# Stemma_Notecard.net
KiCad netlist of a schematic drawn in EAGLE
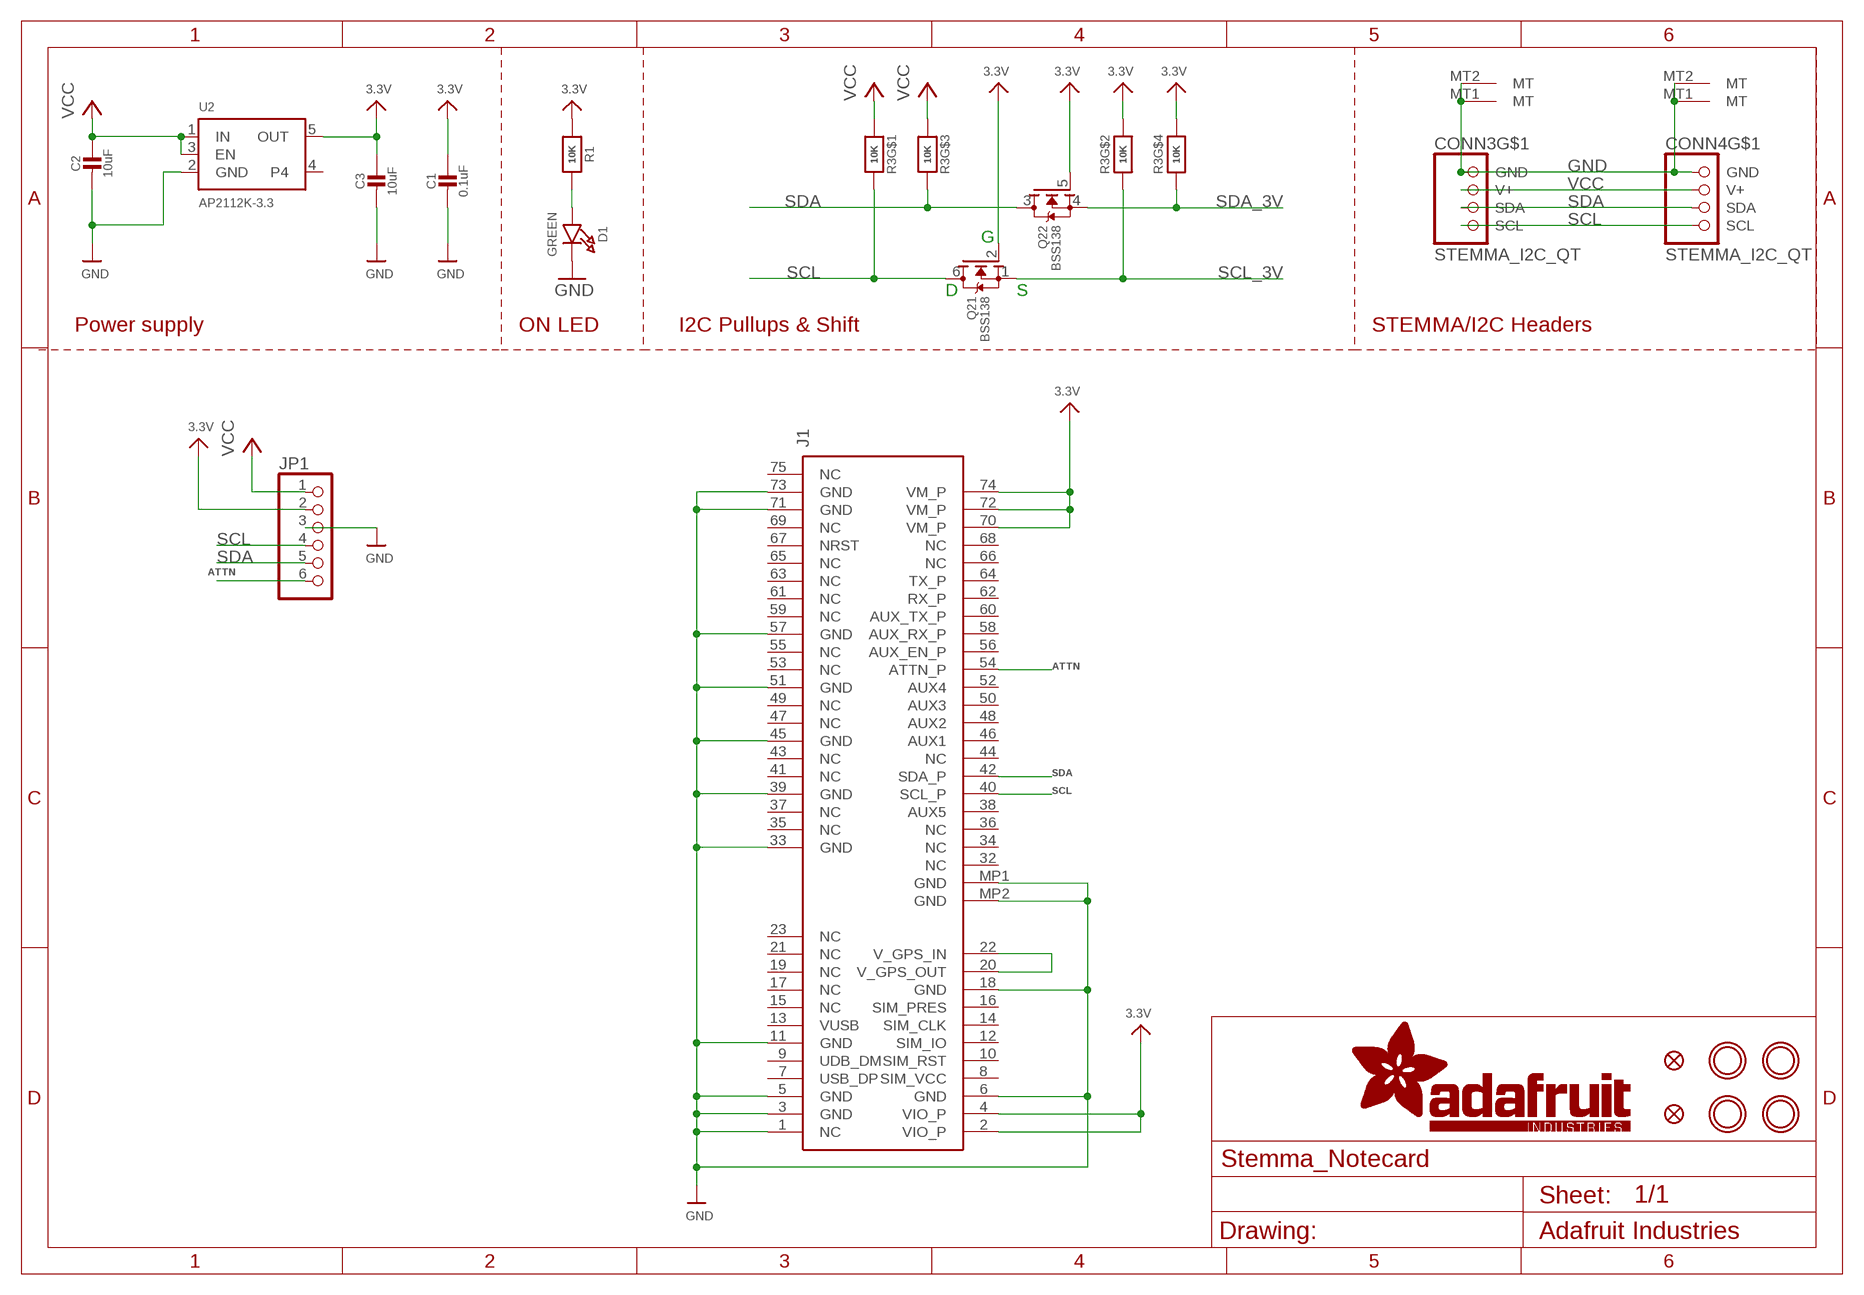
[diagram p0: schematic, sheet 1]

(export (version "E")
  (design (tool "Eeschema 10.0.6"))
  (components
    (comp (ref "C1")
      (value "0.1uF")
      (footprint "eagle-import:0603-NO")
      (libsource (lib "eagle-import") (part "CAP_CERAMIC0603_NO"))
    )
    (comp (ref "C2")
      (value "10uF")
      (footprint "eagle-import:0805-NO")
      (libsource (lib "eagle-import") (part "CAP_CERAMIC0805-NOOUTLINE"))
    )
    (comp (ref "C3")
      (value "10uF")
      (footprint "eagle-import:0805-NO")
      (libsource (lib "eagle-import") (part "CAP_CERAMIC0805-NOOUTLINE"))
    )
    (comp (ref "CONN3")
      (value "STEMMA_I2C_QT")
      (footprint "eagle-import:JST_SH4")
      (libsource (lib "eagle-import") (part "STEMMA_I2C_QT"))
    )
    (comp (ref "CONN4")
      (value "STEMMA_I2C_QT")
      (footprint "eagle-import:JST_SH4")
      (libsource (lib "eagle-import") (part "STEMMA_I2C_QT"))
    )
    (comp (ref "D1")
      (value "GREEN")
      (footprint "eagle-import:CHIPLED_0603_NOOUTLINE")
      (libsource (lib "eagle-import") (part "LED0603_NOOUTLINE"))
    )
    (comp (ref "FID3")
      (value "FIDUCIAL_1MM")
      (footprint "eagle-import:FIDUCIAL_1MM")
      (libsource (lib "eagle-import") (part "FIDUCIAL_1MM"))
    )
    (comp (ref "FID4")
      (value "FIDUCIAL_1MM")
      (footprint "eagle-import:FIDUCIAL_1MM")
      (libsource (lib "eagle-import") (part "FIDUCIAL_1MM"))
    )
    (comp (ref "J1")
      (value "MDT420E01001NOTECARD")
      (footprint "eagle-import:NOTECARD")
      (libsource (lib "eagle-import") (part "MDT420E01001NOTECARD"))
    )
    (comp (ref "JP1")
      (value "HEADER-1X670MIL")
      (footprint "eagle-import:1X06_ROUND_70")
      (libsource (lib "eagle-import") (part "HEADER-1X670MIL"))
    )
    (comp (ref "Q2")
      (value "BSS138")
      (footprint "eagle-import:SOT363")
      (libsource (lib "eagle-import") (part "MOSFET-N_DUAL"))
    )
    (comp (ref "R1")
      (value "10K")
      (footprint "eagle-import:0603-NO")
      (libsource (lib "eagle-import") (part "RESISTOR_0603_NOOUT"))
    )
    (comp (ref "R3")
      (value "10K")
      (footprint "eagle-import:RESPACK_4X0603")
      (libsource (lib "eagle-import") (part "RESISTOR_4PACK"))
    )
    (comp (ref "U$1")
      (value "MOUNTINGHOLE2.5")
      (footprint "eagle-import:MOUNTINGHOLE_2.5_PLATED")
      (libsource (lib "eagle-import") (part "MOUNTINGHOLE2.5"))
    )
    (comp (ref "U$17")
      (value "MOUNTINGHOLE2.5")
      (footprint "eagle-import:MOUNTINGHOLE_2.5_PLATED")
      (libsource (lib "eagle-import") (part "MOUNTINGHOLE2.5"))
    )
    (comp (ref "U$19")
      (value "MOUNTINGHOLE2.5")
      (footprint "eagle-import:MOUNTINGHOLE_2.5_PLATED")
      (libsource (lib "eagle-import") (part "MOUNTINGHOLE2.5"))
    )
    (comp (ref "U$21")
      (value "MOUNTINGHOLE2.5")
      (footprint "eagle-import:MOUNTINGHOLE_2.5_PLATED")
      (libsource (lib "eagle-import") (part "MOUNTINGHOLE2.5"))
    )
    (comp (ref "U2")
      (value "AP2112K-3.3")
      (footprint "eagle-import:SOT23-5")
      (libsource (lib "eagle-import") (part "VREG_SOT23-5"))
    )
  )
  (nets
    (net (code "1") (name "/SCL_3V") (class "Default")
      (node (ref "Q2") (pin "1") (pinfunction "S_1") (pintype "bidirectional"))
      (node (ref "R3") (pin "7") (pinfunction "2_7") (pintype "passive"))
    )
    (net (code "2") (name "/SDA_3V") (class "Default")
      (node (ref "Q2") (pin "4") (pinfunction "S_4") (pintype "bidirectional"))
      (node (ref "R3") (pin "5") (pinfunction "2_5") (pintype "passive"))
    )
    (net (code "3") (name "3.3V") (class "Default")
      (node (ref "C1") (pin "1") (pinfunction "1_1") (pintype "passive"))
      (node (ref "C3") (pin "1") (pinfunction "1_1") (pintype "passive"))
      (node (ref "J1") (pin "2") (pinfunction "VIO_P_2") (pintype "bidirectional"))
      (node (ref "J1") (pin "4") (pinfunction "VIO_P_4") (pintype "bidirectional"))
      (node (ref "J1") (pin "70") (pinfunction "VM_P_70") (pintype "bidirectional"))
      (node (ref "J1") (pin "72") (pinfunction "VM_P_72") (pintype "bidirectional"))
      (node (ref "J1") (pin "74") (pinfunction "VM_P_74") (pintype "bidirectional"))
      (node (ref "JP1") (pin "2") (pinfunction "2_2") (pintype "passive"))
      (node (ref "Q2") (pin "2") (pinfunction "G_2") (pintype "bidirectional"))
      (node (ref "Q2") (pin "5") (pinfunction "G_5") (pintype "bidirectional"))
      (node (ref "R1") (pin "1") (pinfunction "1_1") (pintype "passive"))
      (node (ref "R3") (pin "2") (pinfunction "1_2") (pintype "passive"))
      (node (ref "R3") (pin "4") (pinfunction "1_4") (pintype "passive"))
      (node (ref "U2") (pin "5") (pinfunction "OUT_5") (pintype "power_in"))
    )
    (net (code "4") (name "ATTN") (class "Default")
      (node (ref "J1") (pin "54") (pinfunction "ATTN_P_54") (pintype "bidirectional"))
      (node (ref "JP1") (pin "6") (pinfunction "6_6") (pintype "passive"))
    )
    (net (code "5") (name "GND") (class "Default")
      (node (ref "C1") (pin "2") (pinfunction "2_2") (pintype "passive"))
      (node (ref "C2") (pin "2") (pinfunction "2_2") (pintype "passive"))
      (node (ref "C3") (pin "2") (pinfunction "2_2") (pintype "passive"))
      (node (ref "CONN3") (pin "1") (pinfunction "GND_1") (pintype "passive"))
      (node (ref "CONN3") (pin "MT1") (pinfunction "MT_MT1") (pintype "bidirectional"))
      (node (ref "CONN3") (pin "MT2") (pinfunction "MT_MT2") (pintype "bidirectional"))
      (node (ref "CONN4") (pin "1") (pinfunction "GND_1") (pintype "passive"))
      (node (ref "CONN4") (pin "MT1") (pinfunction "MT_MT1") (pintype "bidirectional"))
      (node (ref "CONN4") (pin "MT2") (pinfunction "MT_MT2") (pintype "bidirectional"))
      (node (ref "D1") (pin "C") (pinfunction "C_C") (pintype "passive"))
      (node (ref "J1") (pin "1") (pinfunction "NC_1") (pintype "bidirectional"))
      (node (ref "J1") (pin "11") (pinfunction "GND_11") (pintype "bidirectional"))
      (node (ref "J1") (pin "18") (pinfunction "GND_18") (pintype "bidirectional"))
      (node (ref "J1") (pin "3") (pinfunction "GND_3") (pintype "bidirectional"))
      (node (ref "J1") (pin "33") (pinfunction "GND_33") (pintype "bidirectional"))
      (node (ref "J1") (pin "39") (pinfunction "GND_39") (pintype "bidirectional"))
      (node (ref "J1") (pin "45") (pinfunction "GND_45") (pintype "bidirectional"))
      (node (ref "J1") (pin "5") (pinfunction "GND_5") (pintype "bidirectional"))
      (node (ref "J1") (pin "51") (pinfunction "GND_51") (pintype "bidirectional"))
      (node (ref "J1") (pin "57") (pinfunction "GND_57") (pintype "bidirectional"))
      (node (ref "J1") (pin "6") (pinfunction "GND_6") (pintype "bidirectional"))
      (node (ref "J1") (pin "71") (pinfunction "GND_71") (pintype "bidirectional"))
      (node (ref "J1") (pin "73") (pinfunction "GND_73") (pintype "bidirectional"))
      (node (ref "J1") (pin "MP1") (pinfunction "GND_MP1") (pintype "power_in"))
      (node (ref "J1") (pin "MP2") (pinfunction "GND_MP2") (pintype "bidirectional"))
      (node (ref "JP1") (pin "3") (pinfunction "3_3") (pintype "passive"))
      (node (ref "U2") (pin "2") (pinfunction "GND_2") (pintype "power_in"))
    )
    (net (code "6") (name "Net-(D1-PadA)") (class "Default")
      (node (ref "D1") (pin "A") (pinfunction "A_A") (pintype "passive"))
      (node (ref "R1") (pin "2") (pinfunction "2_2") (pintype "passive"))
    )
    (net (code "7") (name "Net-(J1-V_GPS_IN)") (class "Default")
      (node (ref "J1") (pin "20") (pinfunction "V_GPS_OUT_20") (pintype "bidirectional"))
      (node (ref "J1") (pin "22") (pinfunction "V_GPS_IN_22") (pintype "bidirectional"))
    )
    (net (code "8") (name "SCL") (class "Default")
      (node (ref "CONN3") (pin "4") (pinfunction "SCL_4") (pintype "passive"))
      (node (ref "CONN4") (pin "4") (pinfunction "SCL_4") (pintype "passive"))
      (node (ref "J1") (pin "40") (pinfunction "SCL_P_40") (pintype "bidirectional"))
      (node (ref "JP1") (pin "4") (pinfunction "4_4") (pintype "passive"))
      (node (ref "Q2") (pin "6") (pinfunction "D_6") (pintype "bidirectional"))
      (node (ref "R3") (pin "8") (pinfunction "2_8") (pintype "passive"))
    )
    (net (code "9") (name "SDA") (class "Default")
      (node (ref "CONN3") (pin "3") (pinfunction "SDA_3") (pintype "passive"))
      (node (ref "CONN4") (pin "3") (pinfunction "SDA_3") (pintype "passive"))
      (node (ref "J1") (pin "42") (pinfunction "SDA_P_42") (pintype "bidirectional"))
      (node (ref "JP1") (pin "5") (pinfunction "5_5") (pintype "passive"))
      (node (ref "Q2") (pin "3") (pinfunction "D_3") (pintype "bidirectional"))
      (node (ref "R3") (pin "6") (pinfunction "2_6") (pintype "passive"))
    )
    (net (code "10") (name "VCC") (class "Default")
      (node (ref "C2") (pin "1") (pinfunction "1_1") (pintype "passive"))
      (node (ref "CONN3") (pin "2") (pinfunction "V+_2") (pintype "passive"))
      (node (ref "CONN4") (pin "2") (pinfunction "V+_2") (pintype "passive"))
      (node (ref "JP1") (pin "1") (pinfunction "1_1") (pintype "passive"))
      (node (ref "R3") (pin "1") (pinfunction "1_1") (pintype "passive"))
      (node (ref "R3") (pin "3") (pinfunction "1_3") (pintype "passive"))
      (node (ref "U2") (pin "1") (pinfunction "IN_1") (pintype "power_in"))
      (node (ref "U2") (pin "3") (pinfunction "EN_3") (pintype "input"))
    )
    (net (code "11") (name "unconnected-(J1-AUX1-Pad46)") (class "Default")
      (node (ref "J1") (pin "46") (pinfunction "AUX1_46") (pintype "bidirectional"))
    )
    (net (code "12") (name "unconnected-(J1-AUX2-Pad48)") (class "Default")
      (node (ref "J1") (pin "48") (pinfunction "AUX2_48") (pintype "bidirectional"))
    )
    (net (code "13") (name "unconnected-(J1-AUX3-Pad50)") (class "Default")
      (node (ref "J1") (pin "50") (pinfunction "AUX3_50") (pintype "bidirectional"))
    )
    (net (code "14") (name "unconnected-(J1-AUX4-Pad52)") (class "Default")
      (node (ref "J1") (pin "52") (pinfunction "AUX4_52") (pintype "bidirectional"))
    )
    (net (code "15") (name "unconnected-(J1-AUX5-Pad38)") (class "Default")
      (node (ref "J1") (pin "38") (pinfunction "AUX5_38") (pintype "bidirectional"))
    )
    (net (code "16") (name "unconnected-(J1-AUX_EN_P-Pad56)") (class "Default")
      (node (ref "J1") (pin "56") (pinfunction "AUX_EN_P_56") (pintype "bidirectional"))
    )
    (net (code "17") (name "unconnected-(J1-AUX_RX_P-Pad58)") (class "Default")
      (node (ref "J1") (pin "58") (pinfunction "AUX_RX_P_58") (pintype "bidirectional"))
    )
    (net (code "18") (name "unconnected-(J1-AUX_TX_P-Pad60)") (class "Default")
      (node (ref "J1") (pin "60") (pinfunction "AUX_TX_P_60") (pintype "bidirectional"))
    )
    (net (code "19") (name "unconnected-(J1-NC-Pad15)") (class "Default")
      (node (ref "J1") (pin "15") (pinfunction "NC_15") (pintype "bidirectional"))
    )
    (net (code "20") (name "unconnected-(J1-NC-Pad17)") (class "Default")
      (node (ref "J1") (pin "17") (pinfunction "NC_17") (pintype "bidirectional"))
    )
    (net (code "21") (name "unconnected-(J1-NC-Pad19)") (class "Default")
      (node (ref "J1") (pin "19") (pinfunction "NC_19") (pintype "bidirectional"))
    )
    (net (code "22") (name "unconnected-(J1-NC-Pad21)") (class "Default")
      (node (ref "J1") (pin "21") (pinfunction "NC_21") (pintype "bidirectional"))
    )
    (net (code "23") (name "unconnected-(J1-NC-Pad23)") (class "Default")
      (node (ref "J1") (pin "23") (pinfunction "NC_23") (pintype "bidirectional"))
    )
    (net (code "24") (name "unconnected-(J1-NC-Pad32)") (class "Default")
      (node (ref "J1") (pin "32") (pinfunction "NC_32") (pintype "bidirectional"))
    )
    (net (code "25") (name "unconnected-(J1-NC-Pad34)") (class "Default")
      (node (ref "J1") (pin "34") (pinfunction "NC_34") (pintype "bidirectional"))
    )
    (net (code "26") (name "unconnected-(J1-NC-Pad35)") (class "Default")
      (node (ref "J1") (pin "35") (pinfunction "NC_35") (pintype "bidirectional"))
    )
    (net (code "27") (name "unconnected-(J1-NC-Pad36)") (class "Default")
      (node (ref "J1") (pin "36") (pinfunction "NC_36") (pintype "bidirectional"))
    )
    (net (code "28") (name "unconnected-(J1-NC-Pad37)") (class "Default")
      (node (ref "J1") (pin "37") (pinfunction "NC_37") (pintype "bidirectional"))
    )
    (net (code "29") (name "unconnected-(J1-NC-Pad41)") (class "Default")
      (node (ref "J1") (pin "41") (pinfunction "NC_41") (pintype "bidirectional"))
    )
    (net (code "30") (name "unconnected-(J1-NC-Pad43)") (class "Default")
      (node (ref "J1") (pin "43") (pinfunction "NC_43") (pintype "bidirectional"))
    )
    (net (code "31") (name "unconnected-(J1-NC-Pad44)") (class "Default")
      (node (ref "J1") (pin "44") (pinfunction "NC_44") (pintype "bidirectional"))
    )
    (net (code "32") (name "unconnected-(J1-NC-Pad47)") (class "Default")
      (node (ref "J1") (pin "47") (pinfunction "NC_47") (pintype "bidirectional"))
    )
    (net (code "33") (name "unconnected-(J1-NC-Pad49)") (class "Default")
      (node (ref "J1") (pin "49") (pinfunction "NC_49") (pintype "bidirectional"))
    )
    (net (code "34") (name "unconnected-(J1-NC-Pad53)") (class "Default")
      (node (ref "J1") (pin "53") (pinfunction "NC_53") (pintype "bidirectional"))
    )
    (net (code "35") (name "unconnected-(J1-NC-Pad55)") (class "Default")
      (node (ref "J1") (pin "55") (pinfunction "NC_55") (pintype "bidirectional"))
    )
    (net (code "36") (name "unconnected-(J1-NC-Pad59)") (class "Default")
      (node (ref "J1") (pin "59") (pinfunction "NC_59") (pintype "bidirectional"))
    )
    (net (code "37") (name "unconnected-(J1-NC-Pad61)") (class "Default")
      (node (ref "J1") (pin "61") (pinfunction "NC_61") (pintype "bidirectional"))
    )
    (net (code "38") (name "unconnected-(J1-NC-Pad63)") (class "Default")
      (node (ref "J1") (pin "63") (pinfunction "NC_63") (pintype "bidirectional"))
    )
    (net (code "39") (name "unconnected-(J1-NC-Pad65)") (class "Default")
      (node (ref "J1") (pin "65") (pinfunction "NC_65") (pintype "bidirectional"))
    )
    (net (code "40") (name "unconnected-(J1-NC-Pad66)") (class "Default")
      (node (ref "J1") (pin "66") (pinfunction "NC_66") (pintype "bidirectional"))
    )
    (net (code "41") (name "unconnected-(J1-NC-Pad68)") (class "Default")
      (node (ref "J1") (pin "68") (pinfunction "NC_68") (pintype "bidirectional"))
    )
    (net (code "42") (name "unconnected-(J1-NC-Pad69)") (class "Default")
      (node (ref "J1") (pin "69") (pinfunction "NC_69") (pintype "bidirectional"))
    )
    (net (code "43") (name "unconnected-(J1-NC-Pad75)") (class "Default")
      (node (ref "J1") (pin "75") (pinfunction "NC_75") (pintype "bidirectional"))
    )
    (net (code "44") (name "unconnected-(J1-NRST-Pad67)") (class "Default")
      (node (ref "J1") (pin "67") (pinfunction "NRST_67") (pintype "bidirectional"))
    )
    (net (code "45") (name "unconnected-(J1-RX_P-Pad62)") (class "Default")
      (node (ref "J1") (pin "62") (pinfunction "RX_P_62") (pintype "bidirectional"))
    )
    (net (code "46") (name "unconnected-(J1-SIM_CLK-Pad14)") (class "Default")
      (node (ref "J1") (pin "14") (pinfunction "SIM_CLK_14") (pintype "bidirectional"))
    )
    (net (code "47") (name "unconnected-(J1-SIM_IO-Pad12)") (class "Default")
      (node (ref "J1") (pin "12") (pinfunction "SIM_IO_12") (pintype "bidirectional"))
    )
    (net (code "48") (name "unconnected-(J1-SIM_PRES-Pad16)") (class "Default")
      (node (ref "J1") (pin "16") (pinfunction "SIM_PRES_16") (pintype "bidirectional"))
    )
    (net (code "49") (name "unconnected-(J1-SIM_RST-Pad10)") (class "Default")
      (node (ref "J1") (pin "10") (pinfunction "SIM_RST_10") (pintype "bidirectional"))
    )
    (net (code "50") (name "unconnected-(J1-SIM_VCC-Pad8)") (class "Default")
      (node (ref "J1") (pin "8") (pinfunction "SIM_VCC_8") (pintype "bidirectional"))
    )
    (net (code "51") (name "unconnected-(J1-TX_P-Pad64)") (class "Default")
      (node (ref "J1") (pin "64") (pinfunction "TX_P_64") (pintype "bidirectional"))
    )
    (net (code "52") (name "unconnected-(J1-UDB_DM-Pad9)") (class "Default")
      (node (ref "J1") (pin "9") (pinfunction "UDB_DM_9") (pintype "bidirectional"))
    )
    (net (code "53") (name "unconnected-(J1-USB_DP-Pad7)") (class "Default")
      (node (ref "J1") (pin "7") (pinfunction "USB_DP_7") (pintype "bidirectional"))
    )
    (net (code "54") (name "unconnected-(J1-VUSB-Pad13)") (class "Default")
      (node (ref "J1") (pin "13") (pinfunction "VUSB_13") (pintype "bidirectional"))
    )
    (net (code "55") (name "unconnected-(U2-P4-Pad4)") (class "Default")
      (node (ref "U2") (pin "4") (pinfunction "P4_4") (pintype "bidirectional"))
    )
  )
)
